# TOP.net
KiCad netlist of a schematic drawn in Altium Designer
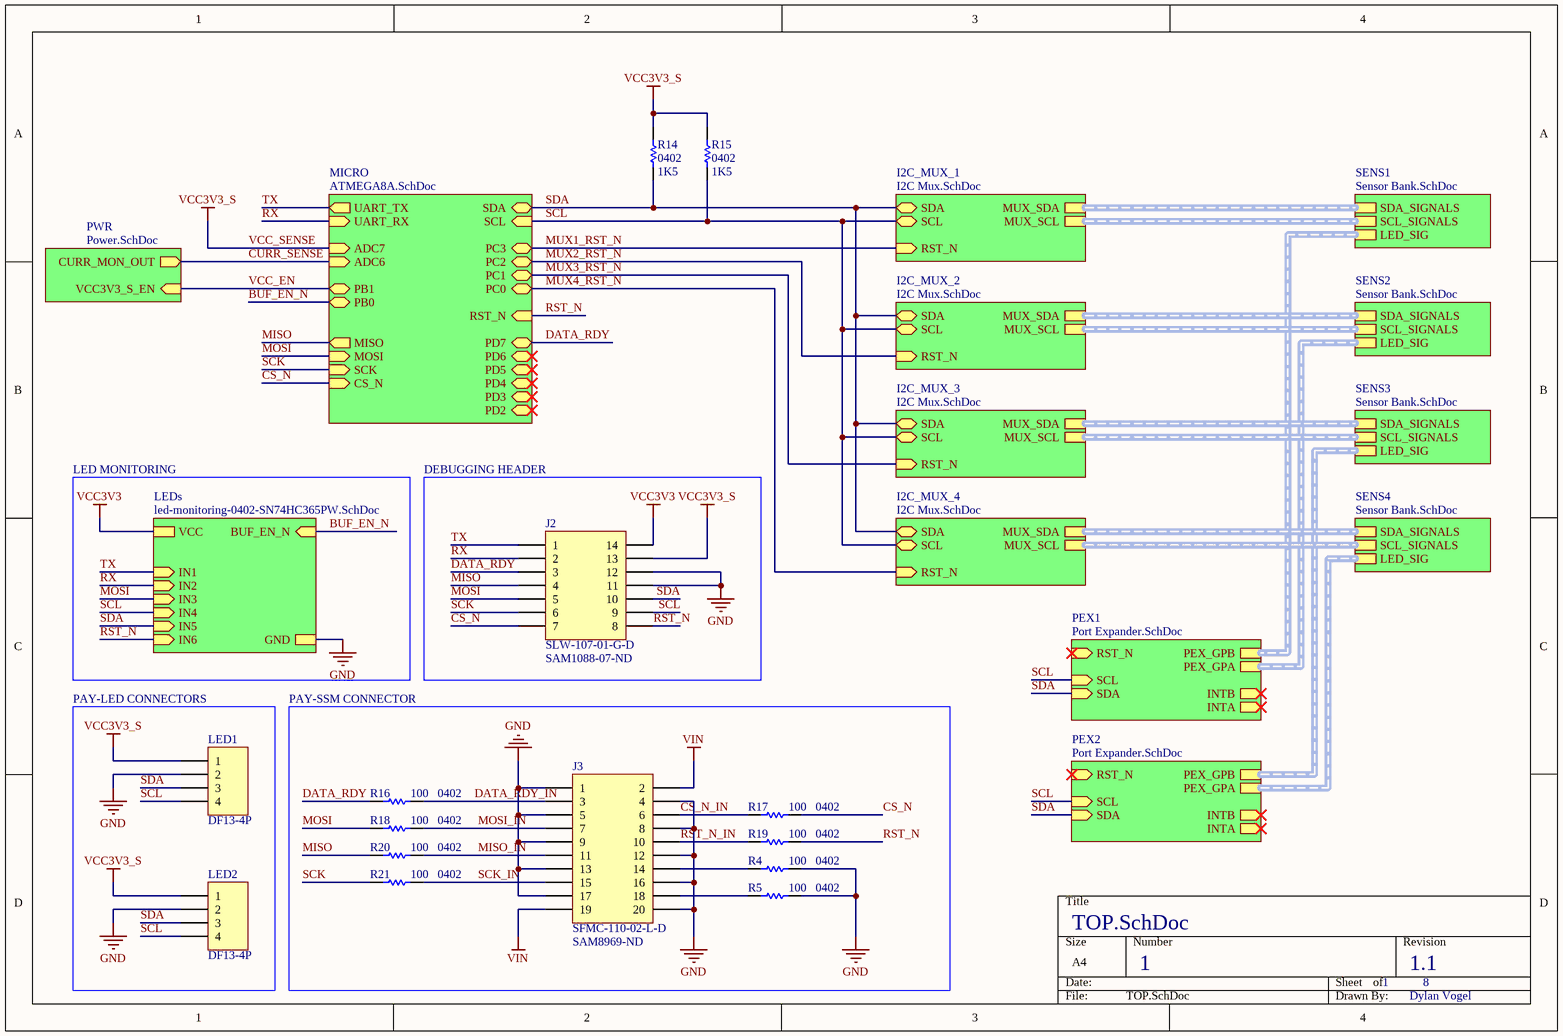
[diagram p0: TOP.SchDoc]

(export (version "E")
  (design (tool "Eeschema 10.0.6"))
  (components
    (comp (ref "J2")
      (value "SLW-107-01-G-D")
      (footprint "SLW-107-01-X-D")
      (fields (field (name "SUPPLIER PART NUMBER 1") "SAM1088-07-ND"))
      (libsource (lib "heron-general") (part "SLW-107-01-G-D"))
    )
    (comp (ref "J3")
      (value "SFMC-110-02-L-D")
      (footprint "SFMC-110-02-L-D")
      (fields (field (name "SUPPLIER PART NUMBER 1") "SAM8969-ND"))
      (libsource (lib "heron-general") (part "SFMC-110-02-L-D"))
    )
    (comp (ref "LED1")
      (value "DF13-4P")
      (footprint "DF13A-4P-1.25H(51)")
      (description "Header, 4-Pin")
      (fields (field (name "PUBLISHER") "Altium Limited"))
      (libsource (lib "Miscellaneous Connectors") (part "Header 4"))
    )
    (comp (ref "LED2")
      (value "DF13-4P")
      (footprint "DF13A-4P-1.25H(51)")
      (description "Header, 4-Pin")
      (fields (field (name "PUBLISHER") "Altium Limited"))
      (libsource (lib "Miscellaneous Connectors") (part "Header 4"))
    )
    (comp (ref "R4")
      (value "0402")
      (footprint "RES0402R")
      (description "Resistor")
      (fields (field (name "ALTIUM_VALUE") "100") (field (name "PUBLISHER") "Altium Limited"))
      (libsource (lib "Miscellaneous Devices") (part "Res1"))
    )
    (comp (ref "R5")
      (value "0402")
      (footprint "RES0402R")
      (description "Resistor")
      (fields (field (name "ALTIUM_VALUE") "100") (field (name "PUBLISHER") "Altium Limited"))
      (libsource (lib "Miscellaneous Devices") (part "Res1"))
    )
    (comp (ref "R14")
      (value "0402")
      (footprint "RES0402R")
      (description "Resistor")
      (fields (field (name "ALTIUM_VALUE") "1K5") (field (name "PUBLISHER") "Altium Limited"))
      (libsource (lib "Miscellaneous Devices") (part "Res1"))
    )
    (comp (ref "R15")
      (value "0402")
      (footprint "RES0402R")
      (description "Resistor")
      (fields (field (name "ALTIUM_VALUE") "1K5") (field (name "PUBLISHER") "Altium Limited"))
      (libsource (lib "Miscellaneous Devices") (part "Res1"))
    )
    (comp (ref "R16")
      (value "0402")
      (footprint "RES0402R")
      (description "Resistor")
      (fields (field (name "ALTIUM_VALUE") "100") (field (name "PUBLISHER") "Altium Limited"))
      (libsource (lib "Miscellaneous Devices") (part "Res1"))
    )
    (comp (ref "R17")
      (value "0402")
      (footprint "RES0402R")
      (description "Resistor")
      (fields (field (name "ALTIUM_VALUE") "100") (field (name "PUBLISHER") "Altium Limited"))
      (libsource (lib "Miscellaneous Devices") (part "Res1"))
    )
    (comp (ref "R18")
      (value "0402")
      (footprint "RES0402R")
      (description "Resistor")
      (fields (field (name "ALTIUM_VALUE") "100") (field (name "PUBLISHER") "Altium Limited"))
      (libsource (lib "Miscellaneous Devices") (part "Res1"))
    )
    (comp (ref "R19")
      (value "0402")
      (footprint "RES0402R")
      (description "Resistor")
      (fields (field (name "ALTIUM_VALUE") "100") (field (name "PUBLISHER") "Altium Limited"))
      (libsource (lib "Miscellaneous Devices") (part "Res1"))
    )
    (comp (ref "R20")
      (value "0402")
      (footprint "RES0402R")
      (description "Resistor")
      (fields (field (name "ALTIUM_VALUE") "100") (field (name "PUBLISHER") "Altium Limited"))
      (libsource (lib "Miscellaneous Devices") (part "Res1"))
    )
    (comp (ref "R21")
      (value "0402")
      (footprint "RES0402R")
      (description "Resistor")
      (fields (field (name "ALTIUM_VALUE") "100") (field (name "PUBLISHER") "Altium Limited"))
      (libsource (lib "Miscellaneous Devices") (part "Res1"))
    )
  )
  (nets
    (net (code "2") (name "/CS_N") (class "Default")
      (node (ref "J2") (pin "13") (pinfunction "7_13") (pintype "passive"))
      (node (ref "R17") (pin "2") (pinfunction "2_2") (pintype "passive"))
    )
    (net (code "3") (name "/CS_N_IN") (class "Default")
      (node (ref "J3") (pin "6") (pinfunction "6_6") (pintype "passive"))
      (node (ref "R17") (pin "1") (pinfunction "1_1") (pintype "passive"))
    )
    (net (code "5") (name "/DATA_RDY") (class "Default")
      (node (ref "J2") (pin "5") (pinfunction "3_5") (pintype "passive"))
      (node (ref "R16") (pin "1") (pinfunction "1_1") (pintype "passive"))
    )
    (net (code "6") (name "/DATA_RDY_IN") (class "Default")
      (node (ref "J3") (pin "3") (pinfunction "3_3") (pintype "passive"))
      (node (ref "R16") (pin "2") (pinfunction "2_2") (pintype "passive"))
    )
    (net (code "15") (name "/MISO") (class "Default")
      (node (ref "J2") (pin "7") (pinfunction "4_7") (pintype "passive"))
      (node (ref "R20") (pin "1") (pinfunction "1_1") (pintype "passive"))
    )
    (net (code "16") (name "/MISO_IN") (class "Default")
      (node (ref "J3") (pin "11") (pinfunction "11_11") (pintype "passive"))
      (node (ref "R20") (pin "2") (pinfunction "2_2") (pintype "passive"))
    )
    (net (code "17") (name "/MOSI") (class "Default")
      (node (ref "J2") (pin "9") (pinfunction "5_9") (pintype "passive"))
      (node (ref "R18") (pin "1") (pinfunction "1_1") (pintype "passive"))
    )
    (net (code "18") (name "/MOSI_IN") (class "Default")
      (node (ref "J3") (pin "7") (pinfunction "7_7") (pintype "passive"))
      (node (ref "R18") (pin "2") (pinfunction "2_2") (pintype "passive"))
    )
    (net (code "36") (name "/RST_N") (class "Default")
      (node (ref "J2") (pin "14") (pinfunction "8_14") (pintype "passive"))
      (node (ref "R19") (pin "2") (pinfunction "2_2") (pintype "passive"))
    )
    (net (code "39") (name "/RST_N_IN") (class "Default")
      (node (ref "J3") (pin "10") (pinfunction "10_10") (pintype "passive"))
      (node (ref "R19") (pin "1") (pinfunction "1_1") (pintype "passive"))
    )
    (net (code "40") (name "/RX") (class "Default")
      (node (ref "J2") (pin "3") (pinfunction "2_3") (pintype "passive"))
    )
    (net (code "41") (name "/SCK") (class "Default")
      (node (ref "J2") (pin "11") (pinfunction "6_11") (pintype "passive"))
      (node (ref "R21") (pin "1") (pinfunction "1_1") (pintype "passive"))
    )
    (net (code "42") (name "/SCK_IN") (class "Default")
      (node (ref "J3") (pin "15") (pinfunction "15_15") (pintype "passive"))
      (node (ref "R21") (pin "2") (pinfunction "2_2") (pintype "passive"))
    )
    (net (code "43") (name "/SCL") (class "Default")
      (node (ref "J2") (pin "12") (pinfunction "9_12") (pintype "passive"))
      (node (ref "LED1") (pin "4") (pinfunction "4_4") (pintype "passive"))
      (node (ref "LED2") (pin "4") (pinfunction "4_4") (pintype "passive"))
      (node (ref "R15") (pin "1") (pinfunction "1_1") (pintype "passive"))
    )
    (net (code "44") (name "/SDA") (class "Default")
      (node (ref "J2") (pin "10") (pinfunction "10_10") (pintype "passive"))
      (node (ref "LED1") (pin "3") (pinfunction "3_3") (pintype "passive"))
      (node (ref "LED2") (pin "3") (pinfunction "3_3") (pintype "passive"))
      (node (ref "R14") (pin "1") (pinfunction "1_1") (pintype "passive"))
    )
    (net (code "45") (name "/TX") (class "Default")
      (node (ref "J2") (pin "1") (pinfunction "1_1") (pintype "passive"))
    )
    (net (code "47") (name "GND") (class "Default")
      (node (ref "J2") (pin "6") (pinfunction "12_6") (pintype "passive"))
      (node (ref "J2") (pin "8") (pinfunction "11_8") (pintype "passive"))
      (node (ref "J3") (pin "1") (pinfunction "1_1") (pintype "passive"))
      (node (ref "J3") (pin "12") (pinfunction "12_12") (pintype "passive"))
      (node (ref "J3") (pin "13") (pinfunction "13_13") (pintype "passive"))
      (node (ref "J3") (pin "16") (pinfunction "16_16") (pintype "passive"))
      (node (ref "J3") (pin "17") (pinfunction "17_17") (pintype "passive"))
      (node (ref "J3") (pin "20") (pinfunction "20_20") (pintype "passive"))
      (node (ref "J3") (pin "4") (pinfunction "4_4") (pintype "passive"))
      (node (ref "J3") (pin "5") (pinfunction "5_5") (pintype "passive"))
      (node (ref "J3") (pin "8") (pinfunction "8_8") (pintype "passive"))
      (node (ref "J3") (pin "9") (pinfunction "9_9") (pintype "passive"))
      (node (ref "LED1") (pin "2") (pinfunction "2_2") (pintype "passive"))
      (node (ref "LED2") (pin "2") (pinfunction "2_2") (pintype "passive"))
      (node (ref "R4") (pin "2") (pinfunction "2_2") (pintype "passive"))
      (node (ref "R5") (pin "2") (pinfunction "2_2") (pintype "passive"))
    )
    (net (code "48") (name "Net-(J3-Pad14)") (class "Default")
      (node (ref "J3") (pin "14") (pinfunction "14_14") (pintype "passive"))
      (node (ref "R4") (pin "1") (pinfunction "1_1") (pintype "passive"))
    )
    (net (code "49") (name "Net-(J3-Pad18)") (class "Default")
      (node (ref "J3") (pin "18") (pinfunction "18_18") (pintype "passive"))
      (node (ref "R5") (pin "1") (pinfunction "1_1") (pintype "passive"))
    )
    (net (code "50") (name "VCC3V3") (class "Default")
      (node (ref "J2") (pin "2") (pinfunction "14_2") (pintype "passive"))
    )
    (net (code "51") (name "VCC3V3_S") (class "Default")
      (node (ref "J2") (pin "4") (pinfunction "13_4") (pintype "passive"))
      (node (ref "LED1") (pin "1") (pinfunction "1_1") (pintype "passive"))
      (node (ref "LED2") (pin "1") (pinfunction "1_1") (pintype "passive"))
      (node (ref "R14") (pin "2") (pinfunction "2_2") (pintype "passive"))
      (node (ref "R15") (pin "2") (pinfunction "2_2") (pintype "passive"))
    )
    (net (code "52") (name "VIN") (class "Default")
      (node (ref "J3") (pin "19") (pinfunction "19_19") (pintype "passive"))
      (node (ref "J3") (pin "2") (pinfunction "2_2") (pintype "passive"))
    )
  )
)
